# AMP_Schem.net
KiCad netlist of a schematic drawn in Altium Designer
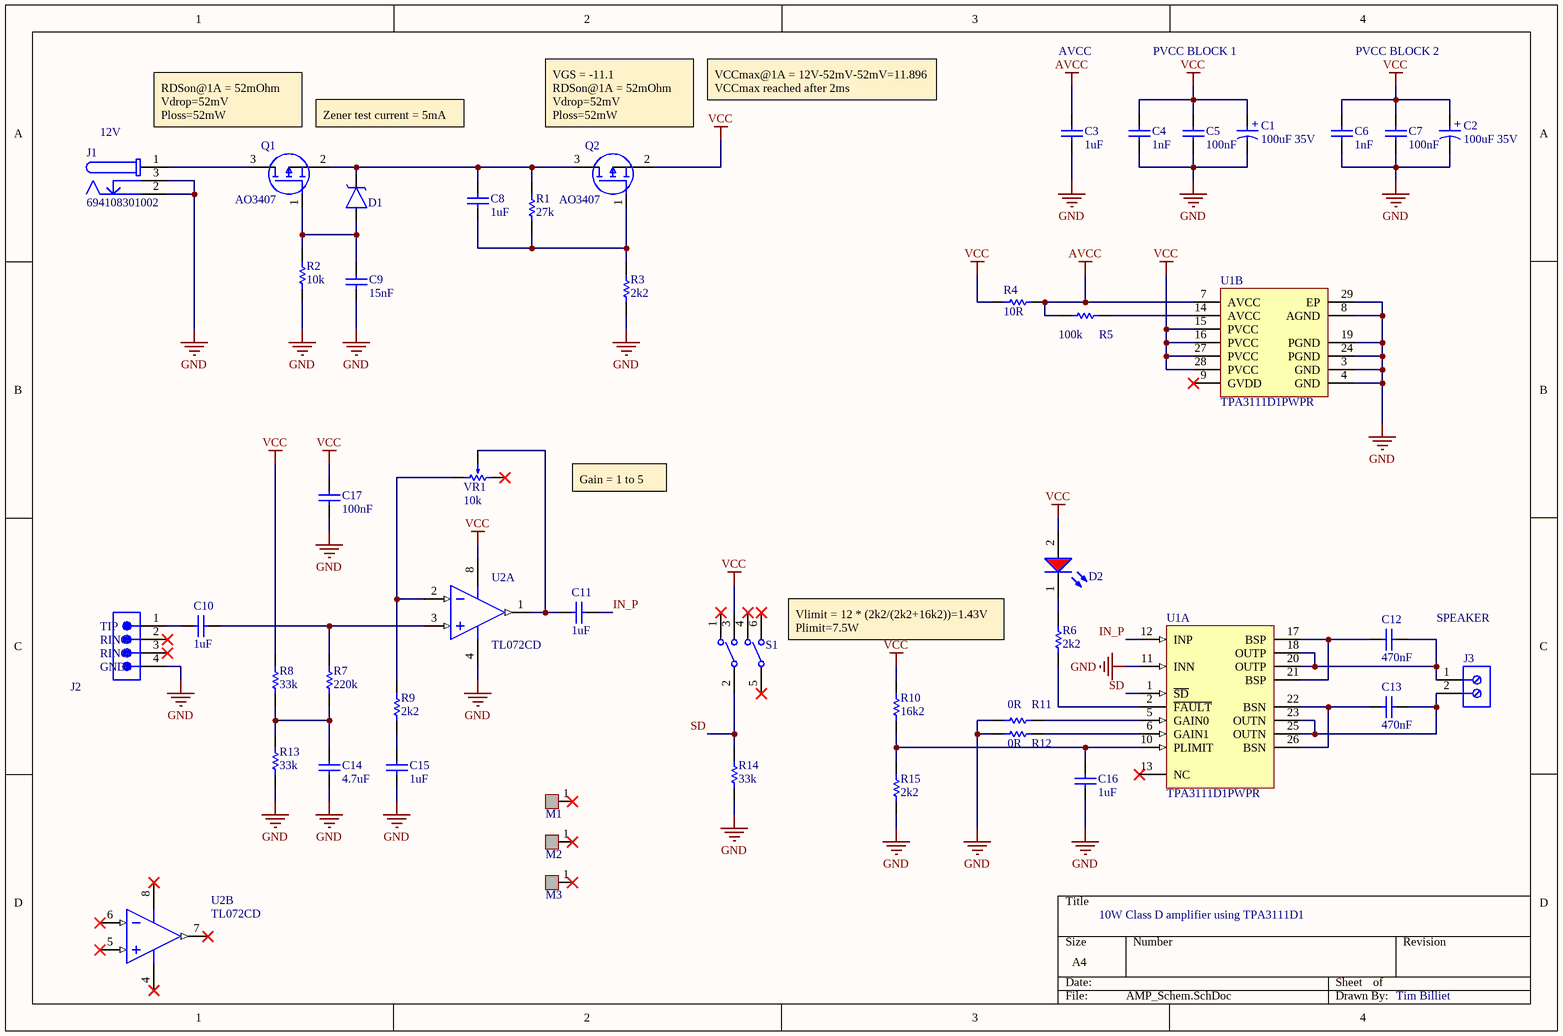
[diagram p0: AMP_Schem.SchDoc]

(export (version "E")
  (design (tool "Eeschema 10.0.6"))
  (components
    (comp (ref "C1")
      (value "100uF 35V")
      (footprint "Wurth D6.3x7.7mm")
      (description "SMD,D6.3xL7.7mm")
      (fields (field (name "Comment") "ROQANG RVT1V101M0607"))
      (libsource (lib "Electrolytic_Capacitors") (part "100uF 35V SMD"))
    )
    (comp (ref "C2")
      (value "100uF 35V")
      (footprint "Wurth D6.3x7.7mm")
      (description "SMD,D6.3xL7.7mm")
      (fields (field (name "Comment") "ROQANG RVT1V101M0607"))
      (libsource (lib "Electrolytic_Capacitors") (part "100uF 35V SMD"))
    )
    (comp (ref "C3")
      (value "1uF")
      (footprint "Wurth 0603 capacitor")
      (fields (field (name "Comment") "Capacitor 1uF 0603"))
      (libsource (lib "Passives") (part "Capacitor 1uF 0603"))
    )
    (comp (ref "C4")
      (value "1nF")
      (footprint "Wurth 0603 capacitor")
      (fields (field (name "Comment") "Capacitor 1nF 0603"))
      (libsource (lib "Passives") (part "Capacitor 1nF 0603"))
    )
    (comp (ref "C5")
      (value "100nF")
      (footprint "Wurth 0603 capacitor")
      (fields (field (name "Comment") "Capacitor 100nF 0603 50V"))
      (libsource (lib "Passives") (part "Capacitor 100nF 0603 50V"))
    )
    (comp (ref "C6")
      (value "1nF")
      (footprint "Wurth 0603 capacitor")
      (fields (field (name "Comment") "Capacitor 1nF 0603"))
      (libsource (lib "Passives") (part "Capacitor 1nF 0603"))
    )
    (comp (ref "C7")
      (value "100nF")
      (footprint "Wurth 0603 capacitor")
      (fields (field (name "Comment") "Capacitor 100nF 0603 50V"))
      (libsource (lib "Passives") (part "Capacitor 100nF 0603 50V"))
    )
    (comp (ref "C8")
      (value "1uF")
      (footprint "Wurth 0603 capacitor")
      (fields (field (name "Comment") "Capacitor 1uF 0603"))
      (libsource (lib "Passives") (part "Capacitor 1uF 0603"))
    )
    (comp (ref "C9")
      (value "15nF")
      (footprint "Wurth 0603 capacitor")
      (fields (field (name "Comment") "Capacitor 15nF 0603"))
      (libsource (lib "Passives") (part "Capacitor 15nF 0603"))
    )
    (comp (ref "C10")
      (value "1uF")
      (footprint "Wurth 0603 capacitor")
      (fields (field (name "Comment") "Capacitor 1uF 0603"))
      (libsource (lib "Passives") (part "Capacitor 1uF 0603"))
    )
    (comp (ref "C11")
      (value "1uF")
      (footprint "Wurth 0603 capacitor")
      (fields (field (name "Comment") "Capacitor 1uF 0603"))
      (libsource (lib "Passives") (part "Capacitor 1uF 0603"))
    )
    (comp (ref "C12")
      (value "470nF")
      (footprint "Wurth 0603 capacitor")
      (fields (field (name "Comment") "Capacitor 470nF 0603 50V"))
      (libsource (lib "Passives") (part "Capacitor 470nF 0603 50V"))
    )
    (comp (ref "C13")
      (value "470nF")
      (footprint "Wurth 0603 capacitor")
      (fields (field (name "Comment") "Capacitor 470nF 0603 50V"))
      (libsource (lib "Passives") (part "Capacitor 470nF 0603 50V"))
    )
    (comp (ref "C14")
      (value "4.7uF")
      (footprint "Wurth 0603 capacitor")
      (fields (field (name "Comment") "Capacitor 4.7uF 0603"))
      (libsource (lib "Passives") (part "Capacitor 4.7uF 0603"))
    )
    (comp (ref "C15")
      (value "1uF")
      (footprint "Wurth 0603 capacitor")
      (fields (field (name "Comment") "Capacitor 1uF 0603"))
      (libsource (lib "Passives") (part "Capacitor 1uF 0603"))
    )
    (comp (ref "C16")
      (value "1uF")
      (footprint "Wurth 0603 capacitor")
      (fields (field (name "Comment") "Capacitor 1uF 0603"))
      (libsource (lib "Passives") (part "Capacitor 1uF 0603"))
    )
    (comp (ref "C17")
      (value "100nF")
      (footprint "Wurth 0603 capacitor")
      (fields (field (name "Comment") "Capacitor 100nF 0603 50V"))
      (libsource (lib "Passives") (part "Capacitor 100nF 0603 50V"))
    )
    (comp (ref "D1")
      (value "BZT52B15V")
      (footprint "SOD-123")
      (libsource (lib "Diodes") (part "YONGYUTAI BZT52B15"))
    )
    (comp (ref "D2")
      (value "Red, 2V, 140°")
      (footprint "Wurth 0603 LED")
      (description "WL-SMCD Mono-color Chip LED Diffused, SMT, size 0603, Red, 2V, 140°")
      (fields
        (field (name "MANUFACTURER PART NUMBER") "150060RS55040")
        (field (name "MANUFACTURER") "Wurth Elektronik")
      )
      (libsource (lib "LED") (part "LED RED 0603"))
    )
    (comp (ref "J1")
      (value "694108301002")
      (footprint "694108301002")
      (description "DC Power Jack Connector WR-DC, Male, Right Angled, THT, 5 A, 24 V")
      (libsource (lib "Altium Content Vault") (part "DC Power Jack"))
    )
    (comp (ref "J2")
      (value "SHOU HAN PJ-320D")
      (footprint "SHOU HAN PJ-320D")
      (libsource (lib "Connectors") (part "3.5mm headphone jack smd"))
    )
    (comp (ref "J3")
      (value "691236510002")
      (footprint "691236510002")
      (description "Terminal Block, Wtb, 2Way, 30-12Awg Rohs Compliant: Yes")
      (libsource (lib "Altium Content Vault") (part "TBL - 1R - 02P - Screw"))
    )
    (comp (ref "M1")
      (value "Mounting hole")
      (footprint "M3 hole")
      (libsource (lib "Mechanical") (part "Mounting hole"))
    )
    (comp (ref "M2")
      (value "Mounting hole")
      (footprint "M3 hole")
      (libsource (lib "Mechanical") (part "Mounting hole"))
    )
    (comp (ref "M3")
      (value "Mounting hole")
      (footprint "M3 hole")
      (libsource (lib "Mechanical") (part "Mounting hole"))
    )
    (comp (ref "Q1")
      (value "AO3407")
      (footprint "UMW SOT23-3")
      (description "MOSFET (P-Channel)")
      (fields (field (name "MANUFACTURER_PART_NUMBER") "AO3407A"))
      (libsource (lib "P_CHN_FET") (part "UMW AO3407A"))
    )
    (comp (ref "Q2")
      (value "AO3407")
      (footprint "UMW SOT23-3")
      (description "MOSFET (P-Channel)")
      (fields (field (name "MANUFACTURER_PART_NUMBER") "AO3407A"))
      (libsource (lib "P_CHN_FET") (part "UMW AO3407A"))
    )
    (comp (ref "R1")
      (value "27k")
      (footprint "Wurth 0603 Resistor")
      (fields (field (name "Comment") "Resistor 27k 0603"))
      (libsource (lib "Passives") (part "Resistor 27k 0603"))
    )
    (comp (ref "R2")
      (value "10k")
      (footprint "Wurth 0603 Resistor")
      (fields (field (name "Comment") "Resistor 10k 0603"))
      (libsource (lib "Passives") (part "Resistor 10k 0603"))
    )
    (comp (ref "R3")
      (value "2k2")
      (footprint "Wurth 0603 Resistor")
      (fields (field (name "Comment") "Resistor 2k2 0603"))
      (libsource (lib "Passives") (part "Resistor 2k2 0603"))
    )
    (comp (ref "R4")
      (value "10R")
      (footprint "Wurth 0603 Resistor")
      (fields (field (name "Comment") "Resistor 10R 0603"))
      (libsource (lib "Passives") (part "Resistor 10R 0603"))
    )
    (comp (ref "R5")
      (value "100k")
      (footprint "Wurth 0603 Resistor")
      (fields (field (name "Comment") "Resistor 100k 0603"))
      (libsource (lib "Passives") (part "Resistor 100k 0603"))
    )
    (comp (ref "R6")
      (value "2k2")
      (footprint "Wurth 0603 Resistor")
      (fields (field (name "Comment") "Resistor 2k2 0603"))
      (libsource (lib "Passives") (part "Resistor 2k2 0603"))
    )
    (comp (ref "R7")
      (value "220k")
      (footprint "Wurth 0603 Resistor")
      (fields (field (name "Comment") "Resistor 220k 0603"))
      (libsource (lib "Passives") (part "Resistor 220k 0603"))
    )
    (comp (ref "R8")
      (value "33k")
      (footprint "Wurth 0603 Resistor")
      (fields (field (name "Comment") "Resistor 33k 0603"))
      (libsource (lib "Passives") (part "Resistor 33k 0603"))
    )
    (comp (ref "R9")
      (value "2k2")
      (footprint "Wurth 0603 Resistor")
      (fields (field (name "Comment") "Resistor 2k2 0603"))
      (libsource (lib "Passives") (part "Resistor 2k2 0603"))
    )
    (comp (ref "R10")
      (value "16k2")
      (footprint "Wurth 0603 Resistor")
      (fields (field (name "Comment") "Resistor 16k2 0603"))
      (libsource (lib "Passives") (part "Resistor 16k2 0603"))
    )
    (comp (ref "R11")
      (value "0R")
      (footprint "Wurth 0603 Resistor")
      (fields (field (name "Comment") "Resistor 0R 0603"))
      (libsource (lib "Passives") (part "Resistor 0R 0603"))
    )
    (comp (ref "R12")
      (value "0R")
      (footprint "Wurth 0603 Resistor")
      (fields (field (name "Comment") "Resistor 0R 0603"))
      (libsource (lib "Passives") (part "Resistor 0R 0603"))
    )
    (comp (ref "R13")
      (value "33k")
      (footprint "Wurth 0603 Resistor")
      (fields (field (name "Comment") "Resistor 33k 0603"))
      (libsource (lib "Passives") (part "Resistor 33k 0603"))
    )
    (comp (ref "R14")
      (value "33k")
      (footprint "Wurth 0603 Resistor")
      (fields (field (name "Comment") "Resistor 33k 0603"))
      (libsource (lib "Passives") (part "Resistor 33k 0603"))
    )
    (comp (ref "R15")
      (value "2k2")
      (footprint "Wurth 0603 Resistor")
      (fields (field (name "Comment") "Resistor 2k2 0603"))
      (libsource (lib "Passives") (part "Resistor 2k2 0603"))
    )
    (comp (ref "S1")
      (value "MST22D18G2 125")
      (footprint "SHOU HAN MST22D18G2 125 switch")
      (libsource (lib "Switches") (part "SHOU HAN MST22D18G2 125"))
    )
    (comp (ref "U1")
      (value "TPA3111D1PWPR")
      (footprint "TI-PWP28-5720X1950TP_N")
      (description "None")
      (libsource (lib "Altium Content Vault") (part "TI-TPA311XD1PWP28-6240X1950TP"))
    )
    (comp (ref "U2")
      (value "TL072CD")
      (footprint "D0008A_M")
      (fields (field (name "MANUFACTURER") "Texas Instruments"))
      (libsource (lib "Altium Content Vault") (part "TI-AMP-D6-2-8_D"))
    )
    (comp (ref "VR1")
      (value "10k")
      (footprint "ALPSALPINE RK09K11300DR")
      (fields (field (name "Comment") "ALPSALPINE RK09K11300DR"))
      (libsource (lib "Passives") (part "Potentiometer 10k"))
    )
  )
  (nets
    (net (code "1") (name "/IN_P") (class "Default")
      (node (ref "C11") (pin "1") (pinfunction "1_1") (pintype "passive"))
      (node (ref "U1") (pin "12") (pinfunction "INP_12") (pintype "input"))
    )
    (net (code "2") (name "/SD") (class "Default")
      (node (ref "R14") (pin "2") (pinfunction "2_2") (pintype "passive"))
      (node (ref "S1") (pin "2") (pinfunction "2_2") (pintype "passive"))
      (node (ref "U1") (pin "1") (pinfunction "~{SD}_1") (pintype "input"))
    )
    (net (code "3") (name "AVCC") (class "Default")
      (node (ref "C3") (pin "2") (pinfunction "2_2") (pintype "passive"))
      (node (ref "R4") (pin "2") (pinfunction "2_2") (pintype "passive"))
      (node (ref "R5") (pin "1") (pinfunction "1_1") (pintype "passive"))
      (node (ref "U1") (pin "7") (pinfunction "AVCC_7") (pintype "power_in"))
    )
    (net (code "4") (name "GND") (class "Default")
      (node (ref "C1") (pin "2") (pinfunction "N_2") (pintype "passive"))
      (node (ref "C14") (pin "1") (pinfunction "1_1") (pintype "passive"))
      (node (ref "C15") (pin "2") (pinfunction "2_2") (pintype "passive"))
      (node (ref "C16") (pin "1") (pinfunction "1_1") (pintype "passive"))
      (node (ref "C17") (pin "1") (pinfunction "1_1") (pintype "passive"))
      (node (ref "C2") (pin "2") (pinfunction "N_2") (pintype "passive"))
      (node (ref "C3") (pin "1") (pinfunction "1_1") (pintype "passive"))
      (node (ref "C4") (pin "1") (pinfunction "1_1") (pintype "passive"))
      (node (ref "C5") (pin "1") (pinfunction "1_1") (pintype "passive"))
      (node (ref "C6") (pin "1") (pinfunction "1_1") (pintype "passive"))
      (node (ref "C7") (pin "1") (pinfunction "1_1") (pintype "passive"))
      (node (ref "C9") (pin "1") (pinfunction "1_1") (pintype "passive"))
      (node (ref "J1") (pin "2") (pinfunction "2_2") (pintype "passive"))
      (node (ref "J1") (pin "3") (pinfunction "3_3") (pintype "passive"))
      (node (ref "J2") (pin "4") (pinfunction "4_4") (pintype "passive"))
      (node (ref "R11") (pin "1") (pinfunction "1_1") (pintype "passive"))
      (node (ref "R12") (pin "1") (pinfunction "1_1") (pintype "passive"))
      (node (ref "R13") (pin "1") (pinfunction "1_1") (pintype "passive"))
      (node (ref "R14") (pin "1") (pinfunction "1_1") (pintype "passive"))
      (node (ref "R15") (pin "1") (pinfunction "1_1") (pintype "passive"))
      (node (ref "R2") (pin "1") (pinfunction "1_1") (pintype "passive"))
      (node (ref "R3") (pin "1") (pinfunction "1_1") (pintype "passive"))
      (node (ref "U1") (pin "11") (pinfunction "INN_11") (pintype "input"))
      (node (ref "U1") (pin "19") (pinfunction "PGND_19") (pintype "power_in"))
      (node (ref "U1") (pin "24") (pinfunction "PGND_24") (pintype "power_in"))
      (node (ref "U1") (pin "29") (pinfunction "EP_29") (pintype "power_in"))
      (node (ref "U1") (pin "3") (pinfunction "GND_3") (pintype "power_in"))
      (node (ref "U1") (pin "4") (pinfunction "GND_4") (pintype "power_in"))
      (node (ref "U1") (pin "8") (pinfunction "AGND_8") (pintype "power_in"))
      (node (ref "U2") (pin "4") (pinfunction "VCC-_4") (pintype "power_in"))
    )
    (net (code "5") (name "Net-(C10-Pad2)") (class "Default")
      (node (ref "C10") (pin "2") (pinfunction "2_2") (pintype "passive"))
      (node (ref "J2") (pin "1") (pinfunction "1_1") (pintype "passive"))
    )
    (net (code "6") (name "Net-(C12-Pad1)") (class "Default")
      (node (ref "C12") (pin "1") (pinfunction "1_1") (pintype "passive"))
      (node (ref "U1") (pin "17") (pinfunction "BSP_17") (pintype "passive"))
      (node (ref "U1") (pin "21") (pinfunction "BSP_21") (pintype "passive"))
    )
    (net (code "7") (name "Net-(C12-Pad2)") (class "Default")
      (node (ref "C12") (pin "2") (pinfunction "2_2") (pintype "passive"))
      (node (ref "J3") (pin "1") (pinfunction "1_1") (pintype "passive"))
      (node (ref "U1") (pin "18") (pinfunction "OUTP_18") (pintype "tri_state"))
      (node (ref "U1") (pin "20") (pinfunction "OUTP_20") (pintype "tri_state"))
    )
    (net (code "8") (name "Net-(C13-Pad1)") (class "Default")
      (node (ref "C13") (pin "1") (pinfunction "1_1") (pintype "passive"))
      (node (ref "U1") (pin "22") (pinfunction "BSN_22") (pintype "passive"))
      (node (ref "U1") (pin "26") (pinfunction "BSN_26") (pintype "passive"))
    )
    (net (code "9") (name "Net-(C13-Pad2)") (class "Default")
      (node (ref "C13") (pin "2") (pinfunction "2_2") (pintype "passive"))
      (node (ref "J3") (pin "2") (pinfunction "2_2") (pintype "passive"))
      (node (ref "U1") (pin "23") (pinfunction "OUTN_23") (pintype "tri_state"))
      (node (ref "U1") (pin "25") (pinfunction "OUTN_25") (pintype "tri_state"))
    )
    (net (code "10") (name "Net-(C14-Pad2)") (class "Default")
      (node (ref "C14") (pin "2") (pinfunction "2_2") (pintype "passive"))
      (node (ref "R13") (pin "2") (pinfunction "2_2") (pintype "passive"))
      (node (ref "R7") (pin "1") (pinfunction "1_1") (pintype "passive"))
      (node (ref "R8") (pin "1") (pinfunction "1_1") (pintype "passive"))
    )
    (net (code "11") (name "Net-(C15-Pad1)") (class "Default")
      (node (ref "C15") (pin "1") (pinfunction "1_1") (pintype "passive"))
      (node (ref "R9") (pin "1") (pinfunction "1_1") (pintype "passive"))
    )
    (net (code "12") (name "Net-(D1-A)") (class "Default")
      (node (ref "C9") (pin "2") (pinfunction "2_2") (pintype "passive"))
      (node (ref "D1") (pin "2") (pinfunction "A_2") (pintype "passive"))
      (node (ref "Q1") (pin "1") (pinfunction "G_1") (pintype "passive"))
      (node (ref "R2") (pin "2") (pinfunction "2_2") (pintype "passive"))
    )
    (net (code "13") (name "Net-(D1-K)") (class "Default")
      (node (ref "C8") (pin "2") (pinfunction "2_2") (pintype "passive"))
      (node (ref "D1") (pin "1") (pinfunction "K_1") (pintype "passive"))
      (node (ref "Q1") (pin "2") (pinfunction "S_2") (pintype "passive"))
      (node (ref "Q2") (pin "3") (pinfunction "D_3") (pintype "passive"))
      (node (ref "R1") (pin "2") (pinfunction "2_2") (pintype "passive"))
    )
    (net (code "14") (name "Net-(D2-K)") (class "Default")
      (node (ref "D2") (pin "1") (pinfunction "K_1") (pintype "passive"))
      (node (ref "R6") (pin "2") (pinfunction "2_2") (pintype "passive"))
    )
    (net (code "15") (name "Net-(Q1-D)") (class "Default")
      (node (ref "J1") (pin "1") (pinfunction "1_1") (pintype "passive"))
      (node (ref "Q1") (pin "3") (pinfunction "D_3") (pintype "passive"))
    )
    (net (code "16") (name "Net-(Q2-G)") (class "Default")
      (node (ref "C8") (pin "1") (pinfunction "1_1") (pintype "passive"))
      (node (ref "Q2") (pin "1") (pinfunction "G_1") (pintype "passive"))
      (node (ref "R1") (pin "1") (pinfunction "1_1") (pintype "passive"))
      (node (ref "R3") (pin "2") (pinfunction "2_2") (pintype "passive"))
    )
    (net (code "17") (name "Net-(R5-Pad2)") (class "Default")
      (node (ref "R5") (pin "2") (pinfunction "2_2") (pintype "passive"))
      (node (ref "U1") (pin "14") (pinfunction "AVCC_14") (pintype "power_in"))
    )
    (net (code "18") (name "Net-(U1A-GAIN0)") (class "Default")
      (node (ref "R11") (pin "2") (pinfunction "2_2") (pintype "passive"))
      (node (ref "U1") (pin "5") (pinfunction "GAIN0_5") (pintype "input"))
    )
    (net (code "19") (name "Net-(U1A-GAIN1)") (class "Default")
      (node (ref "R12") (pin "2") (pinfunction "2_2") (pintype "passive"))
      (node (ref "U1") (pin "6") (pinfunction "GAIN1_6") (pintype "input"))
    )
    (net (code "20") (name "Net-(U1A-PLIMIT)") (class "Default")
      (node (ref "C16") (pin "2") (pinfunction "2_2") (pintype "passive"))
      (node (ref "R10") (pin "1") (pinfunction "1_1") (pintype "passive"))
      (node (ref "R15") (pin "2") (pinfunction "2_2") (pintype "passive"))
      (node (ref "U1") (pin "10") (pinfunction "PLIMIT_10") (pintype "input"))
    )
    (net (code "21") (name "Net-(U1A-~{FAULT})") (class "Default")
      (node (ref "R6") (pin "1") (pinfunction "1_1") (pintype "passive"))
      (node (ref "U1") (pin "2") (pinfunction "~{FAULT}_2") (pintype "open_collector"))
    )
    (net (code "22") (name "Net-(U2A-IN1+)") (class "Default")
      (node (ref "C10") (pin "1") (pinfunction "1_1") (pintype "passive"))
      (node (ref "R7") (pin "2") (pinfunction "2_2") (pintype "passive"))
      (node (ref "U2") (pin "3") (pinfunction "IN1+_3") (pintype "input"))
    )
    (net (code "23") (name "Net-(U2A-IN1-)") (class "Default")
      (node (ref "R9") (pin "2") (pinfunction "2_2") (pintype "passive"))
      (node (ref "U2") (pin "2") (pinfunction "IN1-_2") (pintype "input"))
      (node (ref "VR1") (pin "1") (pinfunction "1_1") (pintype "passive"))
    )
    (net (code "24") (name "Net-(U2A-OUT1)") (class "Default")
      (node (ref "C11") (pin "2") (pinfunction "2_2") (pintype "passive"))
      (node (ref "U2") (pin "1") (pinfunction "OUT1_1") (pintype "output"))
      (node (ref "VR1") (pin "2") (pinfunction "2_2") (pintype "passive"))
    )
    (net (code "25") (name "VCC") (class "Default")
      (node (ref "C1") (pin "1") (pinfunction "P_1") (pintype "passive"))
      (node (ref "C17") (pin "2") (pinfunction "2_2") (pintype "passive"))
      (node (ref "C2") (pin "1") (pinfunction "P_1") (pintype "passive"))
      (node (ref "C4") (pin "2") (pinfunction "2_2") (pintype "passive"))
      (node (ref "C5") (pin "2") (pinfunction "2_2") (pintype "passive"))
      (node (ref "C6") (pin "2") (pinfunction "2_2") (pintype "passive"))
      (node (ref "C7") (pin "2") (pinfunction "2_2") (pintype "passive"))
      (node (ref "D2") (pin "2") (pinfunction "A_2") (pintype "passive"))
      (node (ref "Q2") (pin "2") (pinfunction "S_2") (pintype "passive"))
      (node (ref "R10") (pin "2") (pinfunction "2_2") (pintype "passive"))
      (node (ref "R4") (pin "1") (pinfunction "1_1") (pintype "passive"))
      (node (ref "R8") (pin "2") (pinfunction "2_2") (pintype "passive"))
      (node (ref "S1") (pin "3") (pinfunction "3_3") (pintype "passive"))
      (node (ref "U1") (pin "15") (pinfunction "PVCC_15") (pintype "power_in"))
      (node (ref "U1") (pin "16") (pinfunction "PVCC_16") (pintype "power_in"))
      (node (ref "U1") (pin "27") (pinfunction "PVCC_27") (pintype "power_in"))
      (node (ref "U1") (pin "28") (pinfunction "PVCC_28") (pintype "power_in"))
      (node (ref "U2") (pin "8") (pinfunction "VCC+_8") (pintype "power_in"))
    )
    (net (code "26") (name "unconnected-(J2-Pad2)") (class "Default")
      (node (ref "J2") (pin "2") (pinfunction "2_2") (pintype "passive+no_connect"))
    )
    (net (code "27") (name "unconnected-(J2-Pad3)") (class "Default")
      (node (ref "J2") (pin "3") (pinfunction "3_3") (pintype "passive+no_connect"))
    )
    (net (code "28") (name "unconnected-(M1-Pad1)") (class "Default")
      (node (ref "M1") (pin "1") (pinfunction "1_1") (pintype "passive+no_connect"))
    )
    (net (code "29") (name "unconnected-(M2-Pad1)") (class "Default")
      (node (ref "M2") (pin "1") (pinfunction "1_1") (pintype "passive+no_connect"))
    )
    (net (code "30") (name "unconnected-(M3-Pad1)") (class "Default")
      (node (ref "M3") (pin "1") (pinfunction "1_1") (pintype "passive+no_connect"))
    )
    (net (code "31") (name "unconnected-(S1-Pad1)") (class "Default")
      (node (ref "S1") (pin "1") (pinfunction "1_1") (pintype "passive+no_connect"))
    )
    (net (code "32") (name "unconnected-(S1-Pad4)") (class "Default")
      (node (ref "S1") (pin "4") (pinfunction "4_4") (pintype "passive+no_connect"))
    )
    (net (code "33") (name "unconnected-(S1-Pad5)") (class "Default")
      (node (ref "S1") (pin "5") (pinfunction "5_5") (pintype "passive+no_connect"))
    )
    (net (code "34") (name "unconnected-(S1-Pad6)") (class "Default")
      (node (ref "S1") (pin "6") (pinfunction "6_6") (pintype "passive+no_connect"))
    )
    (net (code "35") (name "unconnected-(U1A-NC-Pad13)") (class "Default")
      (node (ref "U1") (pin "13") (pinfunction "NC_13") (pintype "passive+no_connect"))
    )
    (net (code "36") (name "unconnected-(U1B-GVDD-Pad9)") (class "Default")
      (node (ref "U1") (pin "9") (pinfunction "GVDD_9") (pintype "power_in+no_connect"))
    )
    (net (code "37") (name "unconnected-(U2B-IN2+-Pad5)") (class "Default")
      (node (ref "U2") (pin "5") (pinfunction "IN2+_5") (pintype "input+no_connect"))
    )
    (net (code "38") (name "unconnected-(U2B-IN2--Pad6)") (class "Default")
      (node (ref "U2") (pin "6") (pinfunction "IN2-_6") (pintype "input+no_connect"))
    )
    (net (code "39") (name "unconnected-(U2B-OUT2-Pad7)") (class "Default")
      (node (ref "U2") (pin "7") (pinfunction "OUT2_7") (pintype "output+no_connect"))
    )
    (net (code "40") (name "unconnected-(U2B-VCC+-Pad8)") (class "Default")
      (node (ref "U2") (pin "8") (pinfunction "VCC+_8") (pintype "power_in+no_connect"))
    )
    (net (code "41") (name "unconnected-(U2B-VCC--Pad4)") (class "Default")
      (node (ref "U2") (pin "4") (pinfunction "VCC-_4") (pintype "power_in+no_connect"))
    )
    (net (code "42") (name "unconnected-(VR1-Pad3)") (class "Default")
      (node (ref "VR1") (pin "3") (pinfunction "3_3") (pintype "passive+no_connect"))
    )
  )
)
